# 2022_Tennessee_Competition.net
KiCad netlist of a schematic drawn in EAGLE
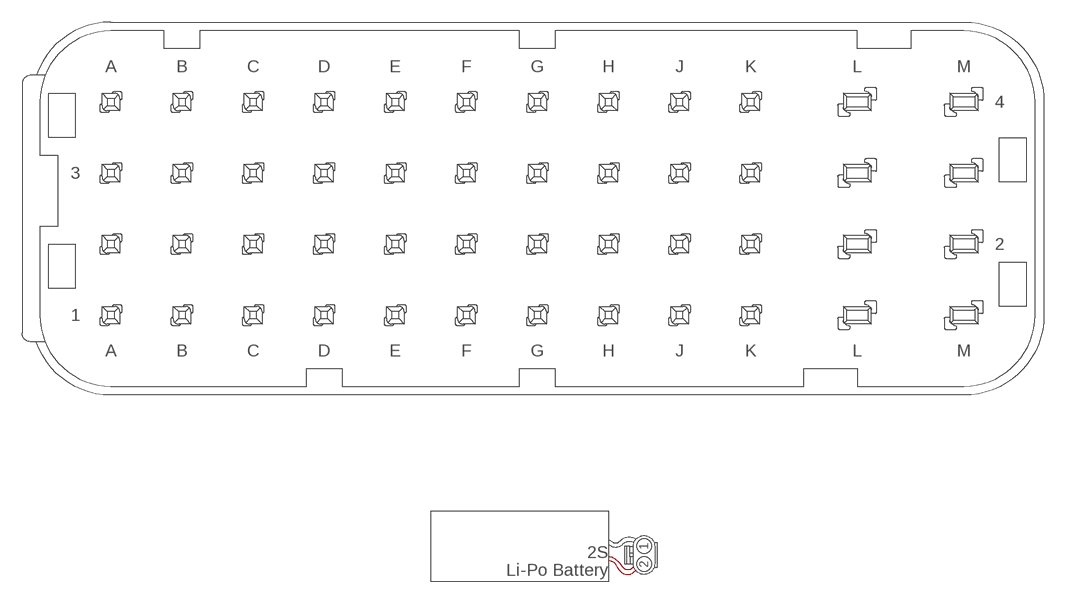
[diagram p0: schematic, sheet 1, part 1 of 2]
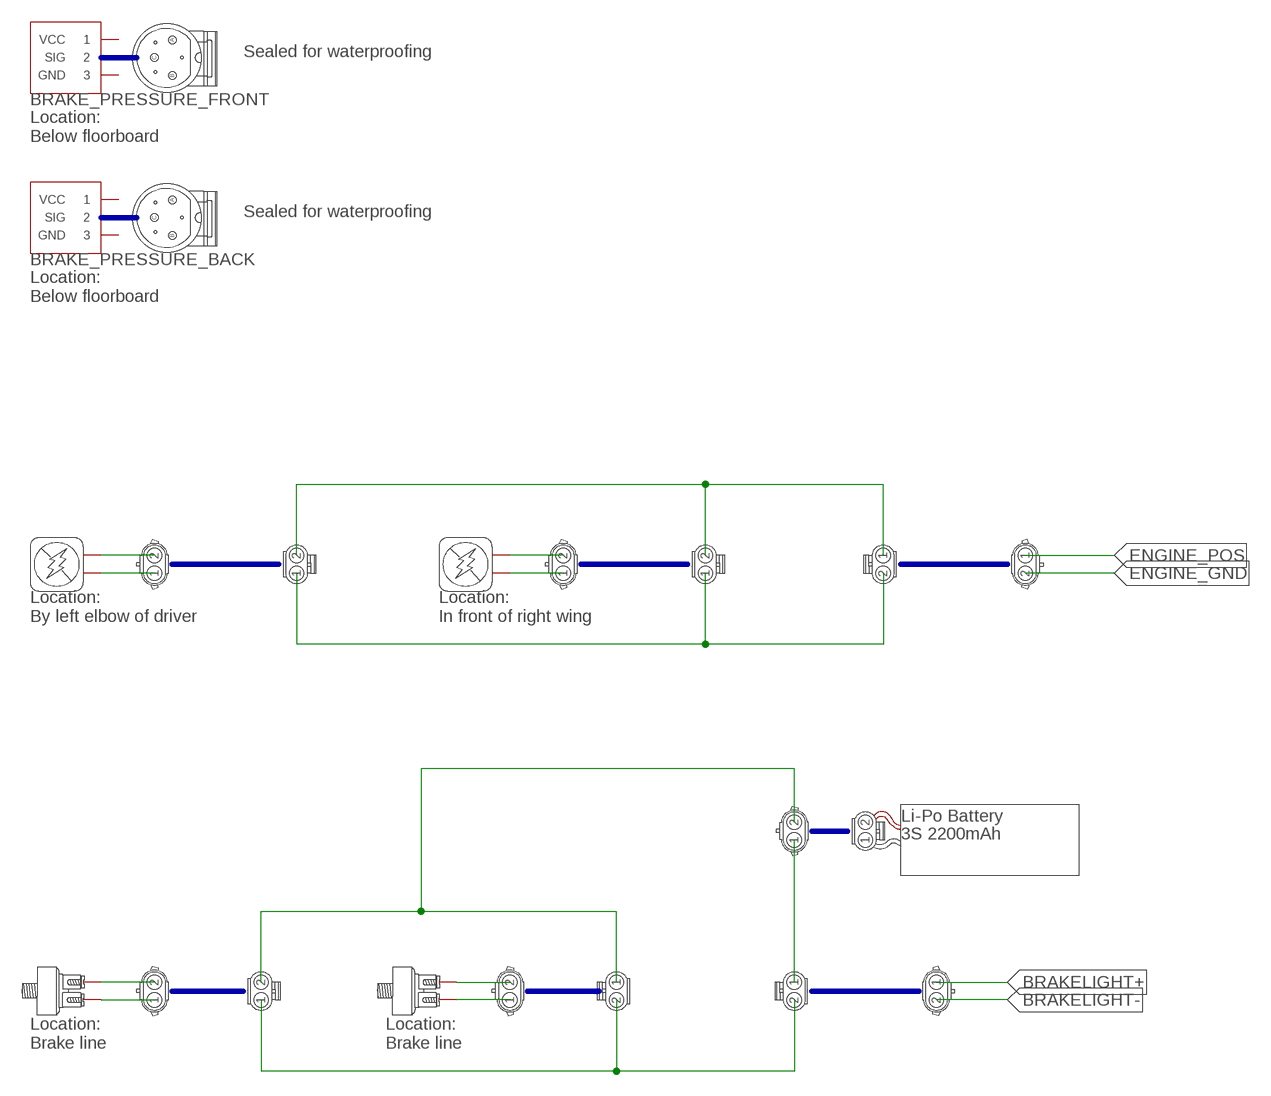
[diagram p1: schematic, sheet 1, part 2 of 2]

(export (version "E")
  (design (tool "Eeschema 10.0.6"))
  (components
    (comp (ref "BRAKE_PRESSURE_BACK")
      (value "SENSOR_1X3")
      (footprint "eagle-import:PINS_3")
      (libsource (lib "eagle-import") (part "SENSOR_1X3"))
    )
    (comp (ref "BRAKE_PRESSURE_FRONT")
      (value "SENSOR_1X3")
      (footprint "eagle-import:PINS_3")
      (libsource (lib "eagle-import") (part "SENSOR_1X3"))
    )
    (comp (ref "U$2")
      (value "CMC_48PIN_PLUG_PCB")
      (footprint "eagle-import:PINS_49")
      (libsource (lib "eagle-import") (part "CMC_48PIN_PLUG_PCB"))
    )
    (comp (ref "U$4")
      (value "SKIDOO_KILLSWITCH")
      (footprint "eagle-import:PINS_3")
      (libsource (lib "eagle-import") (part "SKIDOO_KILLSWITCH"))
    )
    (comp (ref "U$5")
      (value "WEATHERPACK_1X2_MALE")
      (footprint "eagle-import:PINS_3")
      (libsource (lib "eagle-import") (part "WEATHERPACK_1X2_MALE"))
    )
    (comp (ref "U$6")
      (value "WEATHERPACK_1X2_FEMALE")
      (footprint "eagle-import:PINS_3")
      (libsource (lib "eagle-import") (part "WEATHERPACK_1X2_FEMALE"))
    )
    (comp (ref "U$7")
      (value "WEATHERPACK_1X2_MALE")
      (footprint "eagle-import:PINS_3")
      (libsource (lib "eagle-import") (part "WEATHERPACK_1X2_MALE"))
    )
    (comp (ref "U$8")
      (value "WEATHERPACK_1X2_MALE")
      (footprint "eagle-import:PINS_3")
      (libsource (lib "eagle-import") (part "WEATHERPACK_1X2_MALE"))
    )
    (comp (ref "U$9")
      (value "SKIDOO_KILLSWITCH")
      (footprint "eagle-import:PINS_3")
      (libsource (lib "eagle-import") (part "SKIDOO_KILLSWITCH"))
    )
    (comp (ref "U$10")
      (value "WEATHERPACK_1X2_FEMALE")
      (footprint "eagle-import:PINS_3")
      (libsource (lib "eagle-import") (part "WEATHERPACK_1X2_FEMALE"))
    )
    (comp (ref "U$11")
      (value "WEATHERPACK_1X2_FEMALE")
      (footprint "eagle-import:PINS_3")
      (libsource (lib "eagle-import") (part "WEATHERPACK_1X2_FEMALE"))
    )
    (comp (ref "U$12")
      (value "BRAKELIGHT_SWITCH_HYDRAULIC")
      (footprint "eagle-import:PINS_3")
      (libsource (lib "eagle-import") (part "BRAKELIGHT_SWITCH_HYDRAULIC"))
    )
    (comp (ref "U$13")
      (value "WEATHERPACK_1X2_MALE")
      (footprint "eagle-import:PINS_3")
      (libsource (lib "eagle-import") (part "WEATHERPACK_1X2_MALE"))
    )
    (comp (ref "U$15")
      (value "WEATHERPACK_1X2_FEMALE")
      (footprint "eagle-import:PINS_3")
      (libsource (lib "eagle-import") (part "WEATHERPACK_1X2_FEMALE"))
    )
    (comp (ref "U$16")
      (value "WEATHERPACK_1X2_MALE")
      (footprint "eagle-import:PINS_3")
      (libsource (lib "eagle-import") (part "WEATHERPACK_1X2_MALE"))
    )
    (comp (ref "U$17")
      (value "WEATHERPACK_1X2_MALE")
      (footprint "eagle-import:PINS_3")
      (libsource (lib "eagle-import") (part "WEATHERPACK_1X2_MALE"))
    )
    (comp (ref "U$18")
      (value "BRAKELIGHT_SWITCH_HYDRAULIC")
      (footprint "eagle-import:PINS_3")
      (libsource (lib "eagle-import") (part "BRAKELIGHT_SWITCH_HYDRAULIC"))
    )
    (comp (ref "U$19")
      (value "WEATHERPACK_1X2_FEMALE")
      (footprint "eagle-import:PINS_3")
      (libsource (lib "eagle-import") (part "WEATHERPACK_1X2_FEMALE"))
    )
    (comp (ref "U$20")
      (value "WEATHERPACK_1X2_FEMALE")
      (footprint "eagle-import:PINS_3")
      (libsource (lib "eagle-import") (part "WEATHERPACK_1X2_FEMALE"))
    )
    (comp (ref "U$29")
      (value "3S 2200mAh")
      (footprint "eagle-import:PINS_200")
      (libsource (lib "eagle-import") (part "LIPO_BATT"))
    )
    (comp (ref "U$31")
      (value "2S")
      (footprint "eagle-import:PINS_200")
      (libsource (lib "eagle-import") (part "LIPO_BATT"))
    )
    (comp (ref "U$32")
      (value "WEATHERPACK_1X2_MALE")
      (footprint "eagle-import:PINS_3")
      (libsource (lib "eagle-import") (part "WEATHERPACK_1X2_MALE"))
    )
    (comp (ref "U$47")
      (value "METRIPACK_3PIN_FEMALE")
      (footprint "eagle-import:PINS_3")
      (libsource (lib "eagle-import") (part "METRIPACK_3PIN_FEMALE"))
    )
    (comp (ref "U$48")
      (value "METRIPACK_3PIN_FEMALE")
      (footprint "eagle-import:PINS_3")
      (libsource (lib "eagle-import") (part "METRIPACK_3PIN_FEMALE"))
    )
  )
  (nets
    (net (code "2") (name "/L1") (class "Default")
      (node (ref "U$2") (pin "P$41") (pinfunction "L1_P$41") (pintype "power_in"))
    )
    (net (code "3") (name "/L2") (class "Default")
      (node (ref "U$2") (pin "P$42") (pinfunction "L2_P$42") (pintype "power_in"))
    )
    (net (code "4") (name "/L3") (class "Default")
      (node (ref "U$2") (pin "P$43") (pinfunction "L3_P$43") (pintype "power_in"))
    )
    (net (code "5") (name "/L4") (class "Default")
      (node (ref "U$2") (pin "P$44") (pinfunction "L4_P$44") (pintype "power_in"))
    )
    (net (code "6") (name "/M1") (class "Default")
      (node (ref "U$2") (pin "P$45") (pinfunction "M1_P$45") (pintype "power_in"))
    )
    (net (code "7") (name "/M2") (class "Default")
      (node (ref "U$2") (pin "P$46") (pinfunction "M2_P$46") (pintype "power_in"))
    )
    (net (code "8") (name "/M3") (class "Default")
      (node (ref "U$2") (pin "P$47") (pinfunction "M3_P$47") (pintype "power_in"))
    )
    (net (code "9") (name "/M4") (class "Default")
      (node (ref "U$2") (pin "P$48") (pinfunction "M4_P$48") (pintype "power_in"))
    )
    (net (code "11") (name "BRAKELIGHT+") (class "Default")
      (node (ref "U$16") (pin "P$2") (pinfunction "2_P$2") (pintype "bidirectional"))
    )
    (net (code "12") (name "BRAKELIGHT-") (class "Default")
      (node (ref "U$16") (pin "P$1") (pinfunction "1_P$1") (pintype "bidirectional"))
    )
    (net (code "13") (name "ENGINE_GND") (class "Default")
      (node (ref "U$7") (pin "P$1") (pinfunction "1_P$1") (pintype "bidirectional"))
    )
    (net (code "14") (name "ENGINE_POS") (class "Default")
      (node (ref "U$7") (pin "P$2") (pinfunction "2_P$2") (pintype "bidirectional"))
    )
    (net (code "15") (name "Net-(U$5-1)") (class "Default")
      (node (ref "U$4") (pin "P$2") (pinfunction "P$2_P$2") (pintype "bidirectional"))
      (node (ref "U$5") (pin "P$1") (pinfunction "1_P$1") (pintype "bidirectional"))
    )
    (net (code "16") (name "Net-(U$5-2)") (class "Default")
      (node (ref "U$4") (pin "P$1") (pinfunction "P$1_P$1") (pintype "bidirectional"))
      (node (ref "U$5") (pin "P$2") (pinfunction "2_P$2") (pintype "bidirectional"))
    )
    (net (code "17") (name "Net-(U$8-1)") (class "Default")
      (node (ref "U$8") (pin "P$1") (pinfunction "1_P$1") (pintype "bidirectional"))
      (node (ref "U$9") (pin "P$2") (pinfunction "P$2_P$2") (pintype "bidirectional"))
    )
    (net (code "18") (name "Net-(U$8-2)") (class "Default")
      (node (ref "U$8") (pin "P$2") (pinfunction "2_P$2") (pintype "bidirectional"))
      (node (ref "U$9") (pin "P$1") (pinfunction "P$1_P$1") (pintype "bidirectional"))
    )
    (net (code "19") (name "Net-(U$10-1)") (class "Default")
      (node (ref "U$10") (pin "P$1") (pinfunction "1_P$1") (pintype "bidirectional"))
      (node (ref "U$11") (pin "P$2") (pinfunction "2_P$2") (pintype "bidirectional"))
      (node (ref "U$6") (pin "P$1") (pinfunction "1_P$1") (pintype "bidirectional"))
    )
    (net (code "20") (name "Net-(U$10-2)") (class "Default")
      (node (ref "U$10") (pin "P$2") (pinfunction "2_P$2") (pintype "bidirectional"))
      (node (ref "U$11") (pin "P$1") (pinfunction "1_P$1") (pintype "bidirectional"))
      (node (ref "U$6") (pin "P$2") (pinfunction "2_P$2") (pintype "bidirectional"))
    )
    (net (code "21") (name "Net-(U$13-1)") (class "Default")
      (node (ref "U$13") (pin "P$1") (pinfunction "1_P$1") (pintype "bidirectional"))
      (node (ref "U$18") (pin "P$1") (pinfunction "P$1_P$1") (pintype "bidirectional"))
    )
    (net (code "22") (name "Net-(U$13-2)") (class "Default")
      (node (ref "U$13") (pin "P$2") (pinfunction "2_P$2") (pintype "bidirectional"))
      (node (ref "U$18") (pin "P$2") (pinfunction "P$2_P$2") (pintype "bidirectional"))
    )
    (net (code "23") (name "Net-(U$15-1)") (class "Default")
      (node (ref "U$15") (pin "P$1") (pinfunction "1_P$1") (pintype "bidirectional"))
      (node (ref "U$19") (pin "P$2") (pinfunction "2_P$2") (pintype "bidirectional"))
      (node (ref "U$32") (pin "P$1") (pinfunction "1_P$1") (pintype "bidirectional"))
    )
    (net (code "24") (name "Net-(U$15-2)") (class "Default")
      (node (ref "U$15") (pin "P$2") (pinfunction "2_P$2") (pintype "bidirectional"))
      (node (ref "U$19") (pin "P$1") (pinfunction "1_P$1") (pintype "bidirectional"))
      (node (ref "U$20") (pin "P$2") (pinfunction "2_P$2") (pintype "bidirectional"))
    )
    (net (code "25") (name "Net-(U$17-1)") (class "Default")
      (node (ref "U$12") (pin "P$1") (pinfunction "P$1_P$1") (pintype "bidirectional"))
      (node (ref "U$17") (pin "P$1") (pinfunction "1_P$1") (pintype "bidirectional"))
    )
    (net (code "26") (name "Net-(U$17-2)") (class "Default")
      (node (ref "U$12") (pin "P$2") (pinfunction "P$2_P$2") (pintype "bidirectional"))
      (node (ref "U$17") (pin "P$2") (pinfunction "2_P$2") (pintype "bidirectional"))
    )
    (net (code "27") (name "Net-(U$20-1)") (class "Default")
      (node (ref "U$20") (pin "P$1") (pinfunction "1_P$1") (pintype "bidirectional"))
      (node (ref "U$32") (pin "P$2") (pinfunction "2_P$2") (pintype "bidirectional"))
    )
    (net (code "28") (name "unconnected-(BRAKE_PRESSURE_BACK-1-PadP$1)") (class "Default")
      (node (ref "BRAKE_PRESSURE_BACK") (pin "P$1") (pinfunction "1_P$1") (pintype "bidirectional"))
    )
    (net (code "29") (name "unconnected-(BRAKE_PRESSURE_BACK-2-PadP$2)") (class "Default")
      (node (ref "BRAKE_PRESSURE_BACK") (pin "P$2") (pinfunction "2_P$2") (pintype "bidirectional"))
    )
    (net (code "30") (name "unconnected-(BRAKE_PRESSURE_BACK-3-PadP$3)") (class "Default")
      (node (ref "BRAKE_PRESSURE_BACK") (pin "P$3") (pinfunction "3_P$3") (pintype "bidirectional"))
    )
    (net (code "31") (name "unconnected-(BRAKE_PRESSURE_FRONT-1-PadP$1)") (class "Default")
      (node (ref "BRAKE_PRESSURE_FRONT") (pin "P$1") (pinfunction "1_P$1") (pintype "bidirectional"))
    )
    (net (code "32") (name "unconnected-(BRAKE_PRESSURE_FRONT-2-PadP$2)") (class "Default")
      (node (ref "BRAKE_PRESSURE_FRONT") (pin "P$2") (pinfunction "2_P$2") (pintype "bidirectional"))
    )
    (net (code "33") (name "unconnected-(BRAKE_PRESSURE_FRONT-3-PadP$3)") (class "Default")
      (node (ref "BRAKE_PRESSURE_FRONT") (pin "P$3") (pinfunction "3_P$3") (pintype "bidirectional"))
    )
    (net (code "34") (name "unconnected-(U$2-A1-PadP$1)") (class "Default")
      (node (ref "U$2") (pin "P$1") (pinfunction "A1_P$1") (pintype "bidirectional"))
    )
    (net (code "35") (name "unconnected-(U$2-A2-PadP$2)") (class "Default")
      (node (ref "U$2") (pin "P$2") (pinfunction "A2_P$2") (pintype "bidirectional"))
    )
    (net (code "36") (name "unconnected-(U$2-A3-PadP$3)") (class "Default")
      (node (ref "U$2") (pin "P$3") (pinfunction "A3_P$3") (pintype "bidirectional"))
    )
    (net (code "37") (name "unconnected-(U$2-A4-PadP$4)") (class "Default")
      (node (ref "U$2") (pin "P$4") (pinfunction "A4_P$4") (pintype "bidirectional"))
    )
    (net (code "38") (name "unconnected-(U$2-B1-PadP$5)") (class "Default")
      (node (ref "U$2") (pin "P$5") (pinfunction "B1_P$5") (pintype "bidirectional"))
    )
    (net (code "39") (name "unconnected-(U$2-B2-PadP$6)") (class "Default")
      (node (ref "U$2") (pin "P$6") (pinfunction "B2_P$6") (pintype "bidirectional"))
    )
    (net (code "40") (name "unconnected-(U$2-B3-PadP$7)") (class "Default")
      (node (ref "U$2") (pin "P$7") (pinfunction "B3_P$7") (pintype "bidirectional"))
    )
    (net (code "41") (name "unconnected-(U$2-B4-PadP$8)") (class "Default")
      (node (ref "U$2") (pin "P$8") (pinfunction "B4_P$8") (pintype "bidirectional"))
    )
    (net (code "42") (name "unconnected-(U$2-C1-PadP$9)") (class "Default")
      (node (ref "U$2") (pin "P$9") (pinfunction "C1_P$9") (pintype "bidirectional"))
    )
    (net (code "43") (name "unconnected-(U$2-C2-PadP$10)") (class "Default")
      (node (ref "U$2") (pin "P$10") (pinfunction "C2_P$10") (pintype "bidirectional"))
    )
    (net (code "44") (name "unconnected-(U$2-C3-PadP$11)") (class "Default")
      (node (ref "U$2") (pin "P$11") (pinfunction "C3_P$11") (pintype "bidirectional"))
    )
    (net (code "45") (name "unconnected-(U$2-C4-PadP$12)") (class "Default")
      (node (ref "U$2") (pin "P$12") (pinfunction "C4_P$12") (pintype "bidirectional"))
    )
    (net (code "46") (name "unconnected-(U$2-D1-PadP$13)") (class "Default")
      (node (ref "U$2") (pin "P$13") (pinfunction "D1_P$13") (pintype "bidirectional"))
    )
    (net (code "47") (name "unconnected-(U$2-D2-PadP$14)") (class "Default")
      (node (ref "U$2") (pin "P$14") (pinfunction "D2_P$14") (pintype "bidirectional"))
    )
    (net (code "48") (name "unconnected-(U$2-D3-PadP$15)") (class "Default")
      (node (ref "U$2") (pin "P$15") (pinfunction "D3_P$15") (pintype "bidirectional"))
    )
    (net (code "49") (name "unconnected-(U$2-D4-PadP$16)") (class "Default")
      (node (ref "U$2") (pin "P$16") (pinfunction "D4_P$16") (pintype "bidirectional"))
    )
    (net (code "50") (name "unconnected-(U$2-E1-PadP$17)") (class "Default")
      (node (ref "U$2") (pin "P$17") (pinfunction "E1_P$17") (pintype "bidirectional"))
    )
    (net (code "51") (name "unconnected-(U$2-E2-PadP$18)") (class "Default")
      (node (ref "U$2") (pin "P$18") (pinfunction "E2_P$18") (pintype "bidirectional"))
    )
    (net (code "52") (name "unconnected-(U$2-E3-PadP$19)") (class "Default")
      (node (ref "U$2") (pin "P$19") (pinfunction "E3_P$19") (pintype "bidirectional"))
    )
    (net (code "53") (name "unconnected-(U$2-E4-PadP$20)") (class "Default")
      (node (ref "U$2") (pin "P$20") (pinfunction "E4_P$20") (pintype "bidirectional"))
    )
    (net (code "54") (name "unconnected-(U$2-F1-PadP$21)") (class "Default")
      (node (ref "U$2") (pin "P$21") (pinfunction "F1_P$21") (pintype "bidirectional"))
    )
    (net (code "55") (name "unconnected-(U$2-F2-PadP$22)") (class "Default")
      (node (ref "U$2") (pin "P$22") (pinfunction "F2_P$22") (pintype "bidirectional"))
    )
    (net (code "56") (name "unconnected-(U$2-F3-PadP$23)") (class "Default")
      (node (ref "U$2") (pin "P$23") (pinfunction "F3_P$23") (pintype "bidirectional"))
    )
    (net (code "57") (name "unconnected-(U$2-F4-PadP$24)") (class "Default")
      (node (ref "U$2") (pin "P$24") (pinfunction "F4_P$24") (pintype "bidirectional"))
    )
    (net (code "58") (name "unconnected-(U$2-G1-PadP$25)") (class "Default")
      (node (ref "U$2") (pin "P$25") (pinfunction "G1_P$25") (pintype "bidirectional"))
    )
    (net (code "59") (name "unconnected-(U$2-G2-PadP$26)") (class "Default")
      (node (ref "U$2") (pin "P$26") (pinfunction "G2_P$26") (pintype "bidirectional"))
    )
    (net (code "60") (name "unconnected-(U$2-G3-PadP$27)") (class "Default")
      (node (ref "U$2") (pin "P$27") (pinfunction "G3_P$27") (pintype "bidirectional"))
    )
    (net (code "61") (name "unconnected-(U$2-G4-PadP$28)") (class "Default")
      (node (ref "U$2") (pin "P$28") (pinfunction "G4_P$28") (pintype "bidirectional"))
    )
    (net (code "62") (name "unconnected-(U$2-H1-PadP$29)") (class "Default")
      (node (ref "U$2") (pin "P$29") (pinfunction "H1_P$29") (pintype "bidirectional"))
    )
    (net (code "63") (name "unconnected-(U$2-H2-PadP$30)") (class "Default")
      (node (ref "U$2") (pin "P$30") (pinfunction "H2_P$30") (pintype "bidirectional"))
    )
    (net (code "64") (name "unconnected-(U$2-H3-PadP$31)") (class "Default")
      (node (ref "U$2") (pin "P$31") (pinfunction "H3_P$31") (pintype "bidirectional"))
    )
    (net (code "65") (name "unconnected-(U$2-H4-PadP$32)") (class "Default")
      (node (ref "U$2") (pin "P$32") (pinfunction "H4_P$32") (pintype "bidirectional"))
    )
    (net (code "66") (name "unconnected-(U$2-J1-PadP$33)") (class "Default")
      (node (ref "U$2") (pin "P$33") (pinfunction "J1_P$33") (pintype "bidirectional"))
    )
    (net (code "67") (name "unconnected-(U$2-J2-PadP$34)") (class "Default")
      (node (ref "U$2") (pin "P$34") (pinfunction "J2_P$34") (pintype "bidirectional"))
    )
    (net (code "68") (name "unconnected-(U$2-J3-PadP$35)") (class "Default")
      (node (ref "U$2") (pin "P$35") (pinfunction "J3_P$35") (pintype "bidirectional"))
    )
    (net (code "69") (name "unconnected-(U$2-J4-PadP$36)") (class "Default")
      (node (ref "U$2") (pin "P$36") (pinfunction "J4_P$36") (pintype "bidirectional"))
    )
    (net (code "70") (name "unconnected-(U$2-K1-PadP$37)") (class "Default")
      (node (ref "U$2") (pin "P$37") (pinfunction "K1_P$37") (pintype "bidirectional"))
    )
    (net (code "71") (name "unconnected-(U$2-K2-PadP$38)") (class "Default")
      (node (ref "U$2") (pin "P$38") (pinfunction "K2_P$38") (pintype "bidirectional"))
    )
    (net (code "72") (name "unconnected-(U$2-K3-PadP$39)") (class "Default")
      (node (ref "U$2") (pin "P$39") (pinfunction "K3_P$39") (pintype "bidirectional"))
    )
    (net (code "73") (name "unconnected-(U$2-K4-PadP$40)") (class "Default")
      (node (ref "U$2") (pin "P$40") (pinfunction "K4_P$40") (pintype "bidirectional"))
    )
    (net (code "74") (name "unconnected-(U$29-1-PadP$1)") (class "Default")
      (node (ref "U$29") (pin "P$1") (pinfunction "1_P$1") (pintype "bidirectional"))
    )
    (net (code "75") (name "unconnected-(U$29-2-PadP$2)") (class "Default")
      (node (ref "U$29") (pin "P$2") (pinfunction "2_P$2") (pintype "bidirectional"))
    )
    (net (code "76") (name "unconnected-(U$31-1-PadP$1)") (class "Default")
      (node (ref "U$31") (pin "P$1") (pinfunction "1_P$1") (pintype "bidirectional"))
    )
    (net (code "77") (name "unconnected-(U$31-2-PadP$2)") (class "Default")
      (node (ref "U$31") (pin "P$2") (pinfunction "2_P$2") (pintype "bidirectional"))
    )
    (net (code "78") (name "unconnected-(U$47-1-PadP$1)") (class "Default")
      (node (ref "U$47") (pin "P$1") (pinfunction "1_P$1") (pintype "bidirectional"))
    )
    (net (code "79") (name "unconnected-(U$47-2-PadP$2)") (class "Default")
      (node (ref "U$47") (pin "P$2") (pinfunction "2_P$2") (pintype "bidirectional"))
    )
    (net (code "80") (name "unconnected-(U$47-3-PadP$3)") (class "Default")
      (node (ref "U$47") (pin "P$3") (pinfunction "3_P$3") (pintype "bidirectional"))
    )
    (net (code "81") (name "unconnected-(U$48-1-PadP$1)") (class "Default")
      (node (ref "U$48") (pin "P$1") (pinfunction "1_P$1") (pintype "bidirectional"))
    )
    (net (code "82") (name "unconnected-(U$48-2-PadP$2)") (class "Default")
      (node (ref "U$48") (pin "P$2") (pinfunction "2_P$2") (pintype "bidirectional"))
    )
    (net (code "83") (name "unconnected-(U$48-3-PadP$3)") (class "Default")
      (node (ref "U$48") (pin "P$3") (pinfunction "3_P$3") (pintype "bidirectional"))
    )
  )
)
